# lilfoot.net
KiCad netlist of a schematic drawn in Altium Designer
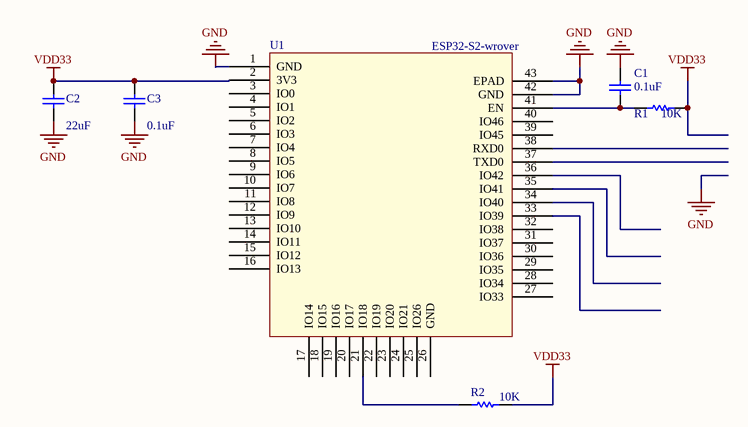
[diagram p0: lilfoot.SchDoc]

(export (version "E")
  (design (tool "Eeschema 10.0.6"))
  (components
    (comp (ref "C1")
      (value "0.1uF")
      (footprint "1608[0603]")
      (description "Capacitor (Semiconductor SIM Model)")
      (fields (field (name "Comment") "Cap Semi") (field (name "PUBLISHER") "Altium Limited"))
      (libsource (lib "Miscellaneous Devices") (part "Cap Semi"))
    )
    (comp (ref "C2")
      (value "22uF")
      (footprint "1608[0603]")
      (description "Capacitor (Semiconductor SIM Model)")
      (fields (field (name "Comment") "Cap Semi") (field (name "PUBLISHER") "Altium Limited"))
      (libsource (lib "Miscellaneous Devices") (part "Cap Semi"))
    )
    (comp (ref "C3")
      (value "0.1uF")
      (footprint "1608[0603]")
      (description "Capacitor (Semiconductor SIM Model)")
      (fields (field (name "Comment") "Cap Semi") (field (name "PUBLISHER") "Altium Limited"))
      (libsource (lib "Miscellaneous Devices") (part "Cap Semi"))
    )
    (comp (ref "R1")
      (value "10K")
      (footprint "1608[0603]")
      (description "Resistor")
      (fields (field (name "Comment") "Res1") (field (name "PUBLISHER") "Altium Limited"))
      (libsource (lib "Miscellaneous Devices") (part "Res1"))
    )
    (comp (ref "R2")
      (value "10K")
      (footprint "1608[0603]")
      (description "Resistor")
      (fields (field (name "Comment") "Res1") (field (name "PUBLISHER") "Altium Limited"))
      (libsource (lib "Miscellaneous Devices") (part "Res1"))
    )
    (comp (ref "U1") (value "ESP32-S2-wrover") (libsource (lib "lilfoot") (part "ESP32-S2-wrover")))
  )
  (nets
    (net (code "1") (name "GND") (class "Default")
      (node (ref "C1") (pin "1") (pinfunction "1_1") (pintype "passive"))
      (node (ref "C2") (pin "2") (pinfunction "2_2") (pintype "passive"))
      (node (ref "C3") (pin "2") (pinfunction "2_2") (pintype "passive"))
      (node (ref "U1") (pin "1") (pinfunction "GND_1") (pintype "passive"))
      (node (ref "U1") (pin "42") (pinfunction "GND_42") (pintype "passive"))
      (node (ref "U1") (pin "43") (pinfunction "EPAD_43") (pintype "passive"))
    )
    (net (code "2") (name "Net-(U1-EN)") (class "Default")
      (node (ref "C1") (pin "2") (pinfunction "2_2") (pintype "passive"))
      (node (ref "R1") (pin "1") (pinfunction "1_1") (pintype "passive"))
      (node (ref "U1") (pin "41") (pinfunction "EN_41") (pintype "passive"))
    )
    (net (code "3") (name "Net-(U1-IO18)") (class "Default")
      (node (ref "R2") (pin "1") (pinfunction "1_1") (pintype "passive"))
      (node (ref "U1") (pin "21") (pinfunction "IO18_21") (pintype "passive"))
    )
    (net (code "4") (name "VDD33") (class "Default")
      (node (ref "C2") (pin "1") (pinfunction "1_1") (pintype "passive"))
      (node (ref "C3") (pin "1") (pinfunction "1_1") (pintype "passive"))
      (node (ref "R1") (pin "2") (pinfunction "2_2") (pintype "passive"))
      (node (ref "R2") (pin "2") (pinfunction "2_2") (pintype "passive"))
      (node (ref "U1") (pin "2") (pinfunction "3V3_2") (pintype "passive"))
    )
    (net (code "5") (name "unconnected-(U1-GND-Pad26)") (class "Default")
      (node (ref "U1") (pin "26") (pinfunction "GND_26") (pintype "passive"))
    )
    (net (code "6") (name "unconnected-(U1-IO0-Pad3)") (class "Default")
      (node (ref "U1") (pin "3") (pinfunction "IO0_3") (pintype "passive"))
    )
    (net (code "7") (name "unconnected-(U1-IO1-Pad4)") (class "Default")
      (node (ref "U1") (pin "4") (pinfunction "IO1_4") (pintype "passive"))
    )
    (net (code "8") (name "unconnected-(U1-IO2-Pad5)") (class "Default")
      (node (ref "U1") (pin "5") (pinfunction "IO2_5") (pintype "passive"))
    )
    (net (code "9") (name "unconnected-(U1-IO3-Pad6)") (class "Default")
      (node (ref "U1") (pin "6") (pinfunction "IO3_6") (pintype "passive"))
    )
    (net (code "10") (name "unconnected-(U1-IO4-Pad7)") (class "Default")
      (node (ref "U1") (pin "7") (pinfunction "IO4_7") (pintype "passive"))
    )
    (net (code "11") (name "unconnected-(U1-IO5-Pad8)") (class "Default")
      (node (ref "U1") (pin "8") (pinfunction "IO5_8") (pintype "passive"))
    )
    (net (code "12") (name "unconnected-(U1-IO6-Pad9)") (class "Default")
      (node (ref "U1") (pin "9") (pinfunction "IO6_9") (pintype "passive"))
    )
    (net (code "13") (name "unconnected-(U1-IO7-Pad10)") (class "Default")
      (node (ref "U1") (pin "10") (pinfunction "IO7_10") (pintype "passive"))
    )
    (net (code "14") (name "unconnected-(U1-IO8-Pad11)") (class "Default")
      (node (ref "U1") (pin "11") (pinfunction "IO8_11") (pintype "passive"))
    )
    (net (code "15") (name "unconnected-(U1-IO9-Pad12)") (class "Default")
      (node (ref "U1") (pin "12") (pinfunction "IO9_12") (pintype "passive"))
    )
    (net (code "16") (name "unconnected-(U1-IO10-Pad13)") (class "Default")
      (node (ref "U1") (pin "13") (pinfunction "IO10_13") (pintype "passive"))
    )
    (net (code "17") (name "unconnected-(U1-IO11-Pad14)") (class "Default")
      (node (ref "U1") (pin "14") (pinfunction "IO11_14") (pintype "passive"))
    )
    (net (code "18") (name "unconnected-(U1-IO12-Pad15)") (class "Default")
      (node (ref "U1") (pin "15") (pinfunction "IO12_15") (pintype "passive"))
    )
    (net (code "19") (name "unconnected-(U1-IO13-Pad16)") (class "Default")
      (node (ref "U1") (pin "16") (pinfunction "IO13_16") (pintype "passive"))
    )
    (net (code "20") (name "unconnected-(U1-IO14-Pad17)") (class "Default")
      (node (ref "U1") (pin "17") (pinfunction "IO14_17") (pintype "passive"))
    )
    (net (code "21") (name "unconnected-(U1-IO15-Pad18)") (class "Default")
      (node (ref "U1") (pin "18") (pinfunction "IO15_18") (pintype "passive"))
    )
    (net (code "22") (name "unconnected-(U1-IO16-Pad19)") (class "Default")
      (node (ref "U1") (pin "19") (pinfunction "IO16_19") (pintype "passive"))
    )
    (net (code "23") (name "unconnected-(U1-IO17-Pad20)") (class "Default")
      (node (ref "U1") (pin "20") (pinfunction "IO17_20") (pintype "passive"))
    )
    (net (code "24") (name "unconnected-(U1-IO19-Pad22)") (class "Default")
      (node (ref "U1") (pin "22") (pinfunction "IO19_22") (pintype "passive"))
    )
    (net (code "25") (name "unconnected-(U1-IO20-Pad23)") (class "Default")
      (node (ref "U1") (pin "23") (pinfunction "IO20_23") (pintype "passive"))
    )
    (net (code "26") (name "unconnected-(U1-IO21-Pad24)") (class "Default")
      (node (ref "U1") (pin "24") (pinfunction "IO21_24") (pintype "passive"))
    )
    (net (code "27") (name "unconnected-(U1-IO26-Pad25)") (class "Default")
      (node (ref "U1") (pin "25") (pinfunction "IO26_25") (pintype "passive"))
    )
    (net (code "28") (name "unconnected-(U1-IO33-Pad27)") (class "Default")
      (node (ref "U1") (pin "27") (pinfunction "IO33_27") (pintype "passive"))
    )
    (net (code "29") (name "unconnected-(U1-IO34-Pad28)") (class "Default")
      (node (ref "U1") (pin "28") (pinfunction "IO34_28") (pintype "passive"))
    )
    (net (code "30") (name "unconnected-(U1-IO35-Pad29)") (class "Default")
      (node (ref "U1") (pin "29") (pinfunction "IO35_29") (pintype "passive"))
    )
    (net (code "31") (name "unconnected-(U1-IO36-Pad30)") (class "Default")
      (node (ref "U1") (pin "30") (pinfunction "IO36_30") (pintype "passive"))
    )
    (net (code "32") (name "unconnected-(U1-IO37-Pad31)") (class "Default")
      (node (ref "U1") (pin "31") (pinfunction "IO37_31") (pintype "passive"))
    )
    (net (code "33") (name "unconnected-(U1-IO38-Pad32)") (class "Default")
      (node (ref "U1") (pin "32") (pinfunction "IO38_32") (pintype "passive"))
    )
    (net (code "34") (name "unconnected-(U1-IO39-Pad33)") (class "Default")
      (node (ref "U1") (pin "33") (pinfunction "IO39_33") (pintype "passive"))
    )
    (net (code "35") (name "unconnected-(U1-IO40-Pad34)") (class "Default")
      (node (ref "U1") (pin "34") (pinfunction "IO40_34") (pintype "passive"))
    )
    (net (code "36") (name "unconnected-(U1-IO41-Pad35)") (class "Default")
      (node (ref "U1") (pin "35") (pinfunction "IO41_35") (pintype "passive"))
    )
    (net (code "37") (name "unconnected-(U1-IO42-Pad36)") (class "Default")
      (node (ref "U1") (pin "36") (pinfunction "IO42_36") (pintype "passive"))
    )
    (net (code "38") (name "unconnected-(U1-IO45-Pad39)") (class "Default")
      (node (ref "U1") (pin "39") (pinfunction "IO45_39") (pintype "passive"))
    )
    (net (code "39") (name "unconnected-(U1-IO46-Pad40)") (class "Default")
      (node (ref "U1") (pin "40") (pinfunction "IO46_40") (pintype "passive"))
    )
    (net (code "40") (name "unconnected-(U1-RXD0-Pad38)") (class "Default")
      (node (ref "U1") (pin "38") (pinfunction "RXD0_38") (pintype "passive"))
    )
    (net (code "41") (name "unconnected-(U1-TXD0-Pad37)") (class "Default")
      (node (ref "U1") (pin "37") (pinfunction "TXD0_37") (pintype "passive"))
    )
  )
)
